# P10_ATMEGA328P1.net
KiCad netlist of a schematic drawn in Altium Designer
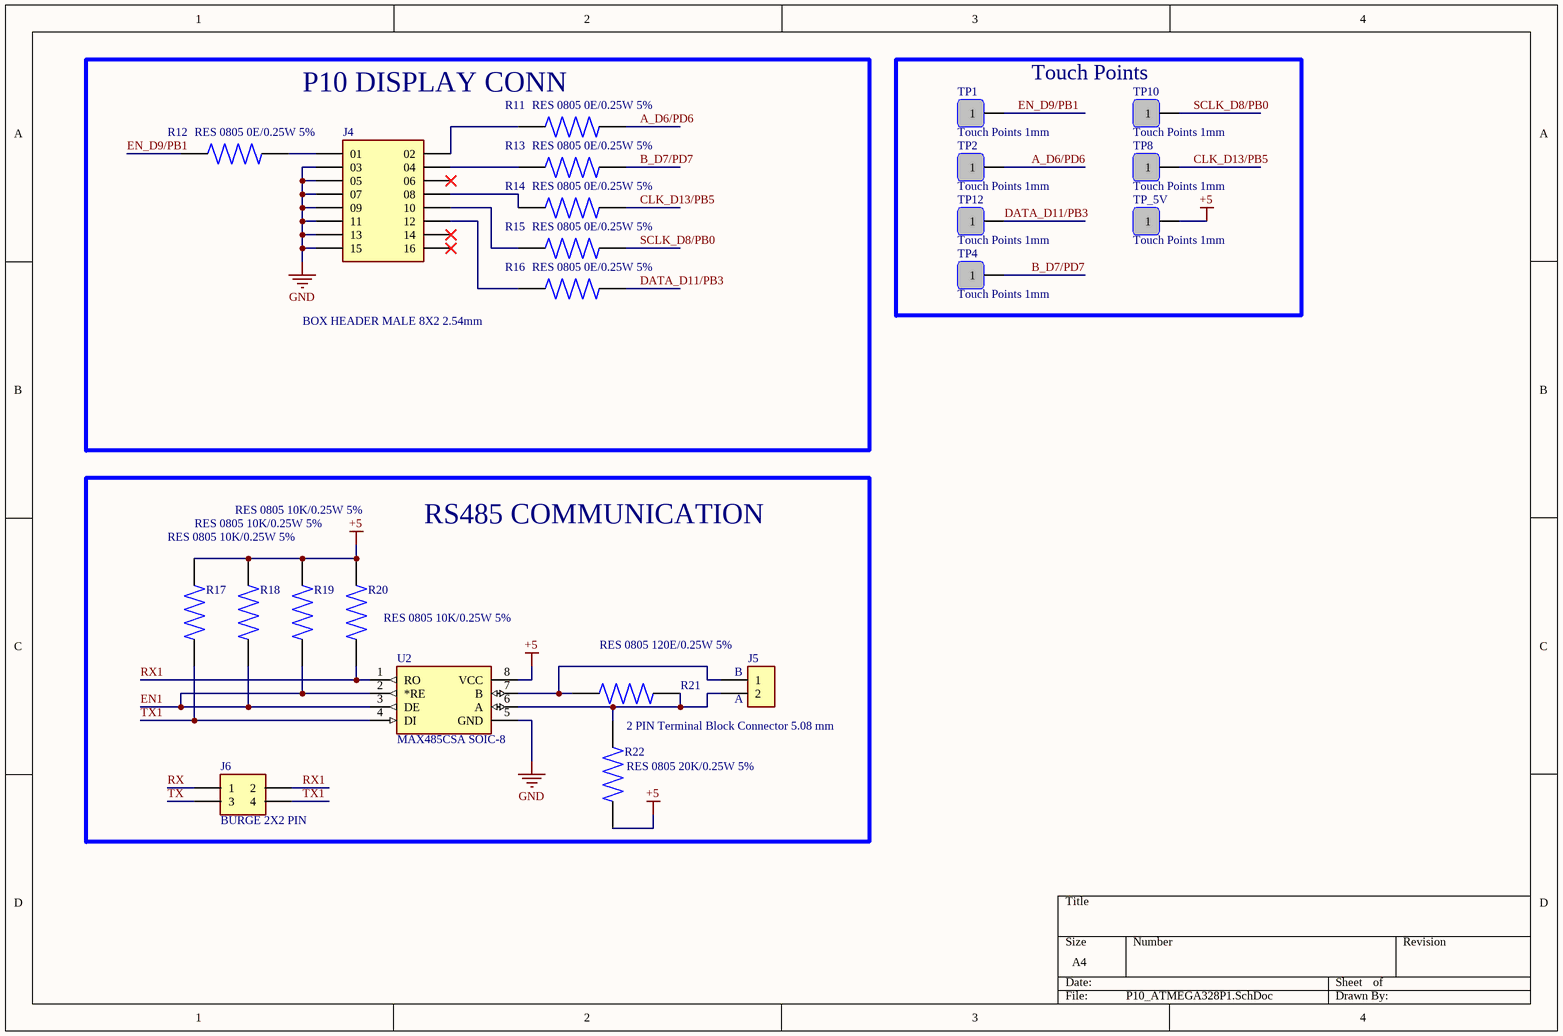
[diagram p0: P10_ATMEGA328P1.SchDoc]

(export (version "E")
  (design (tool "Eeschema 10.0.6"))
  (components
    (comp (ref "J4")
      (value "BOX HEADER MALE 8X2 2.54mm")
      (footprint "BOX HEADER MALE 8X2 2.54mm")
      (description "BOX HEADER MALE 8X2 2.54mm 16 pin")
      (fields (field (name "MP") "TSS-108-01-T-D"))
      (libsource (lib "P10_ATMEGA328P") (part "BOX HEADER MALE 8X2 2.54mm"))
    )
    (comp (ref "J5")
      (value "2 PIN Terminal Block Connector 5.08 mm")
      (footprint "2 PIN Terminal Block Connector 5.08 mm")
      (description "MOLEX,Screw Type, Horizontal, 5.08 Pitch, 24~12 (AWG), Terminal Block Connector, TB007-508-02BE")
      (fields (field (name "MF") "Same Sky") (field (name "MP") "TB007-508-02BE"))
      (libsource (lib "P10_ATMEGA328P") (part "2 PIN Terminal Block Connector 5.08 mm"))
    )
    (comp (ref "J6")
      (value "BURGE 2X2 PIN")
      (footprint "BURGE 2X2 pin")
      (description "Connector Header Through Hole 4 position 0.100 (2.54mm), 2X2 PIN")
      (fields (field (name "MF") "Samtec") (field (name "MP") "MTLW-102-05-G-D-180"))
      (libsource (lib "P10_ATMEGA328P") (part "4PIN BURGE"))
    )
    (comp (ref "R11")
      (value "RES 0805 0E/0.25W 5%")
      (footprint "RES 0805 10K/0.25W 5%")
      (fields (field (name "MP") "ERJ-6GEYJ103V") (field (name "MF") "Panasonic Electronic"))
      (libsource (lib "P10_ATMEGA328P") (part "RES 0805 10K/0.25W 5%"))
    )
    (comp (ref "R12")
      (value "RES 0805 0E/0.25W 5%")
      (footprint "RES 0805 10K/0.25W 5%")
      (fields (field (name "MP") "ERJ-6GEYJ103V") (field (name "MF") "Panasonic Electronic"))
      (libsource (lib "P10_ATMEGA328P") (part "RES 0805 10K/0.25W 5%"))
    )
    (comp (ref "R13")
      (value "RES 0805 0E/0.25W 5%")
      (footprint "RES 0805 10K/0.25W 5%")
      (fields (field (name "MP") "ERJ-6GEYJ103V") (field (name "MF") "Panasonic Electronic"))
      (libsource (lib "P10_ATMEGA328P") (part "RES 0805 10K/0.25W 5%"))
    )
    (comp (ref "R14")
      (value "RES 0805 0E/0.25W 5%")
      (footprint "RES 0805 10K/0.25W 5%")
      (fields (field (name "MP") "ERJ-6GEYJ103V") (field (name "MF") "Panasonic Electronic"))
      (libsource (lib "P10_ATMEGA328P") (part "RES 0805 10K/0.25W 5%"))
    )
    (comp (ref "R15")
      (value "RES 0805 0E/0.25W 5%")
      (footprint "RES 0805 10K/0.25W 5%")
      (fields (field (name "MP") "ERJ-6GEYJ103V") (field (name "MF") "Panasonic Electronic"))
      (libsource (lib "P10_ATMEGA328P") (part "RES 0805 10K/0.25W 5%"))
    )
    (comp (ref "R16")
      (value "RES 0805 0E/0.25W 5%")
      (footprint "RES 0805 10K/0.25W 5%")
      (fields (field (name "MP") "ERJ-6GEYJ103V") (field (name "MF") "Panasonic Electronic"))
      (libsource (lib "P10_ATMEGA328P") (part "RES 0805 10K/0.25W 5%"))
    )
    (comp (ref "R17")
      (value "RES 0805 10K/0.25W 5%")
      (footprint "RES 0805 10K/0.25W 5%")
      (fields (field (name "MP") "ERJ-6GEYJ103V") (field (name "MF") "Panasonic Electronic"))
      (libsource (lib "P10_ATMEGA328P") (part "RES 0805 10K/0.25W 5%"))
    )
    (comp (ref "R18")
      (value "RES 0805 10K/0.25W 5%")
      (footprint "RES 0805 10K/0.25W 5%")
      (fields (field (name "MP") "ERJ-6GEYJ103V") (field (name "MF") "Panasonic Electronic"))
      (libsource (lib "P10_ATMEGA328P") (part "RES 0805 10K/0.25W 5%"))
    )
    (comp (ref "R19")
      (value "RES 0805 10K/0.25W 5%")
      (footprint "RES 0805 10K/0.25W 5%")
      (fields (field (name "MP") "ERJ-6GEYJ103V") (field (name "MF") "Panasonic Electronic"))
      (libsource (lib "P10_ATMEGA328P") (part "RES 0805 10K/0.25W 5%"))
    )
    (comp (ref "R20")
      (value "RES 0805 10K/0.25W 5%")
      (footprint "RES 0805 10K/0.25W 5%")
      (fields (field (name "MP") "ERJ-6GEYJ103V") (field (name "MF") "Panasonic Electronic"))
      (libsource (lib "P10_ATMEGA328P") (part "RES 0805 10K/0.25W 5%"))
    )
    (comp (ref "R21")
      (value "RES 0805 120E/0.25W 5%")
      (footprint "RES 0805 10K/0.25W 5%")
      (fields (field (name "MP") "ERJ-6GEYJ103V") (field (name "MF") "Panasonic Electronic"))
      (libsource (lib "P10_ATMEGA328P") (part "RES 0805 10K/0.25W 5%"))
    )
    (comp (ref "R22")
      (value "RES 0805 20K/0.25W 5%")
      (footprint "RES 0805 10K/0.25W 5%")
      (fields (field (name "MP") "ERJ-6GEYJ103V") (field (name "MF") "Panasonic Electronic"))
      (libsource (lib "P10_ATMEGA328P") (part "RES 0805 10K/0.25W 5%"))
    )
    (comp (ref "TP1")
      (value "Touch Points 1mm")
      (footprint "Touch Points 1mm")
      (description "Touch Points 0.75mm to1mm")
      (libsource (lib "P10_ESP32") (part "Touch Points"))
    )
    (comp (ref "TP2")
      (value "Touch Points 1mm")
      (footprint "Touch Points 1mm")
      (description "Touch Points 0.75mm to1mm")
      (libsource (lib "P10_ESP32") (part "Touch Points"))
    )
    (comp (ref "TP4")
      (value "Touch Points 1mm")
      (footprint "Touch Points 1mm")
      (description "Touch Points 0.75mm to1mm")
      (libsource (lib "P10_ESP32") (part "Touch Points"))
    )
    (comp (ref "TP8")
      (value "Touch Points 1mm")
      (footprint "Touch Points 1mm")
      (description "Touch Points 0.75mm to1mm")
      (libsource (lib "P10_ESP32") (part "Touch Points"))
    )
    (comp (ref "TP10")
      (value "Touch Points 1mm")
      (footprint "Touch Points 1mm")
      (description "Touch Points 0.75mm to1mm")
      (libsource (lib "P10_ESP32") (part "Touch Points"))
    )
    (comp (ref "TP12")
      (value "Touch Points 1mm")
      (footprint "Touch Points 1mm")
      (description "Touch Points 0.75mm to1mm")
      (libsource (lib "P10_ESP32") (part "Touch Points"))
    )
    (comp (ref "TP_5V")
      (value "Touch Points 1mm")
      (footprint "Touch Points 1mm")
      (description "Touch Points 0.75mm to1mm")
      (libsource (lib "P10_ESP32") (part "Touch Points"))
    )
    (comp (ref "U2")
      (value "MAX485CSA SOIC-8")
      (footprint "MAX485CSA")
      (description "MAX485CSA-RS-485/RS-422 Transceivers, SOIC-8")
      (fields (field (name "MF") "Analog Devices") (field (name "MP") "MAX485CSA+"))
      (libsource (lib "P10_ATMEGA328P") (part "MAX485CSA"))
    )
  )
  (nets
    (net (code "1") (name "+5") (class "Default")
      (node (ref "R17") (pin "2") (pinfunction "2_2") (pintype "passive"))
      (node (ref "R18") (pin "2") (pinfunction "2_2") (pintype "passive"))
      (node (ref "R19") (pin "2") (pinfunction "2_2") (pintype "passive"))
      (node (ref "R20") (pin "2") (pinfunction "2_2") (pintype "passive"))
      (node (ref "R22") (pin "1") (pinfunction "1_1") (pintype "passive"))
      (node (ref "TP_5V") (pin "1") (pinfunction "1_1") (pintype "passive"))
      (node (ref "U2") (pin "8") (pinfunction "VCC_8") (pintype "power_in"))
    )
    (net (code "2") (name "/A_D6{slash}PD6") (class "Default")
      (node (ref "R11") (pin "2") (pinfunction "2_2") (pintype "passive"))
      (node (ref "TP2") (pin "1") (pinfunction "1_1") (pintype "passive"))
    )
    (net (code "3") (name "/B_D7{slash}PD7") (class "Default")
      (node (ref "R13") (pin "2") (pinfunction "2_2") (pintype "passive"))
      (node (ref "TP4") (pin "1") (pinfunction "1_1") (pintype "passive"))
    )
    (net (code "4") (name "/CLK_D13{slash}PB5") (class "Default")
      (node (ref "R14") (pin "2") (pinfunction "2_2") (pintype "passive"))
      (node (ref "TP8") (pin "1") (pinfunction "1_1") (pintype "passive"))
    )
    (net (code "5") (name "/DATA_D11{slash}PB3") (class "Default")
      (node (ref "R16") (pin "2") (pinfunction "2_2") (pintype "passive"))
      (node (ref "TP12") (pin "1") (pinfunction "1_1") (pintype "passive"))
    )
    (net (code "6") (name "/EN1") (class "Default")
      (node (ref "R18") (pin "1") (pinfunction "1_1") (pintype "passive"))
      (node (ref "R19") (pin "1") (pinfunction "1_1") (pintype "passive"))
      (node (ref "U2") (pin "2") (pinfunction "*RE_2") (pintype "output"))
      (node (ref "U2") (pin "3") (pinfunction "DE_3") (pintype "output"))
    )
    (net (code "7") (name "/EN_D9{slash}PB1") (class "Default")
      (node (ref "R12") (pin "1") (pinfunction "1_1") (pintype "passive"))
      (node (ref "TP1") (pin "1") (pinfunction "1_1") (pintype "passive"))
    )
    (net (code "8") (name "/RX") (class "Default")
      (node (ref "J6") (pin "01") (pinfunction "1_01") (pintype "passive"))
    )
    (net (code "9") (name "/RX1") (class "Default")
      (node (ref "J6") (pin "02") (pinfunction "2_02") (pintype "passive"))
      (node (ref "R20") (pin "1") (pinfunction "1_1") (pintype "passive"))
      (node (ref "U2") (pin "1") (pinfunction "RO_1") (pintype "output"))
    )
    (net (code "10") (name "/SCLK_D8{slash}PB0") (class "Default")
      (node (ref "R15") (pin "2") (pinfunction "2_2") (pintype "passive"))
      (node (ref "TP10") (pin "1") (pinfunction "1_1") (pintype "passive"))
    )
    (net (code "11") (name "/TX") (class "Default")
      (node (ref "J6") (pin "03") (pinfunction "3_03") (pintype "passive"))
    )
    (net (code "12") (name "/TX1") (class "Default")
      (node (ref "J6") (pin "04") (pinfunction "4_04") (pintype "passive"))
      (node (ref "R17") (pin "1") (pinfunction "1_1") (pintype "passive"))
      (node (ref "U2") (pin "4") (pinfunction "DI_4") (pintype "input"))
    )
    (net (code "13") (name "GND") (class "Default")
      (node (ref "J4") (pin "03") (pinfunction "03_03") (pintype "passive"))
      (node (ref "J4") (pin "05") (pinfunction "05_05") (pintype "passive"))
      (node (ref "J4") (pin "07") (pinfunction "07_07") (pintype "passive"))
      (node (ref "J4") (pin "09") (pinfunction "09_09") (pintype "passive"))
      (node (ref "J4") (pin "11") (pinfunction "11_11") (pintype "passive"))
      (node (ref "J4") (pin "13") (pinfunction "13_13") (pintype "passive"))
      (node (ref "J4") (pin "15") (pinfunction "15_15") (pintype "passive"))
      (node (ref "U2") (pin "5") (pinfunction "GND_5") (pintype "power_in"))
    )
    (net (code "14") (name "Net-(J4-Pad01)") (class "Default")
      (node (ref "J4") (pin "01") (pinfunction "01_01") (pintype "passive"))
      (node (ref "R12") (pin "2") (pinfunction "2_2") (pintype "passive"))
    )
    (net (code "15") (name "Net-(J4-Pad02)") (class "Default")
      (node (ref "J4") (pin "02") (pinfunction "02_02") (pintype "passive"))
      (node (ref "R11") (pin "1") (pinfunction "1_1") (pintype "passive"))
    )
    (net (code "16") (name "Net-(J4-Pad04)") (class "Default")
      (node (ref "J4") (pin "04") (pinfunction "04_04") (pintype "passive"))
      (node (ref "R13") (pin "1") (pinfunction "1_1") (pintype "passive"))
    )
    (net (code "17") (name "Net-(J4-Pad08)") (class "Default")
      (node (ref "J4") (pin "08") (pinfunction "08_08") (pintype "passive"))
      (node (ref "R14") (pin "1") (pinfunction "1_1") (pintype "passive"))
    )
    (net (code "18") (name "Net-(J4-Pad10)") (class "Default")
      (node (ref "J4") (pin "10") (pinfunction "10_10") (pintype "passive"))
      (node (ref "R15") (pin "1") (pinfunction "1_1") (pintype "passive"))
    )
    (net (code "19") (name "Net-(J4-Pad12)") (class "Default")
      (node (ref "J4") (pin "12") (pinfunction "12_12") (pintype "passive"))
      (node (ref "R16") (pin "1") (pinfunction "1_1") (pintype "passive"))
    )
    (net (code "20") (name "Net-(U2-A)") (class "Default")
      (node (ref "J5") (pin "2") (pinfunction "2_2") (pintype "passive"))
      (node (ref "R21") (pin "2") (pinfunction "2_2") (pintype "passive"))
      (node (ref "R22") (pin "2") (pinfunction "2_2") (pintype "passive"))
      (node (ref "U2") (pin "6") (pinfunction "A_6") (pintype "bidirectional"))
    )
    (net (code "21") (name "Net-(U2-B)") (class "Default")
      (node (ref "J5") (pin "1") (pinfunction "1_1") (pintype "passive"))
      (node (ref "R21") (pin "1") (pinfunction "1_1") (pintype "passive"))
      (node (ref "U2") (pin "7") (pinfunction "B_7") (pintype "bidirectional"))
    )
    (net (code "22") (name "unconnected-(J4-Pad06)") (class "Default")
      (node (ref "J4") (pin "06") (pinfunction "06_06") (pintype "passive+no_connect"))
    )
    (net (code "23") (name "unconnected-(J4-Pad14)") (class "Default")
      (node (ref "J4") (pin "14") (pinfunction "14_14") (pintype "passive+no_connect"))
    )
    (net (code "24") (name "unconnected-(J4-Pad16)") (class "Default")
      (node (ref "J4") (pin "16") (pinfunction "16_16") (pintype "passive+no_connect"))
    )
  )
)
